# Sheet3_Bat.net
KiCad netlist of a schematic drawn in Altium Designer
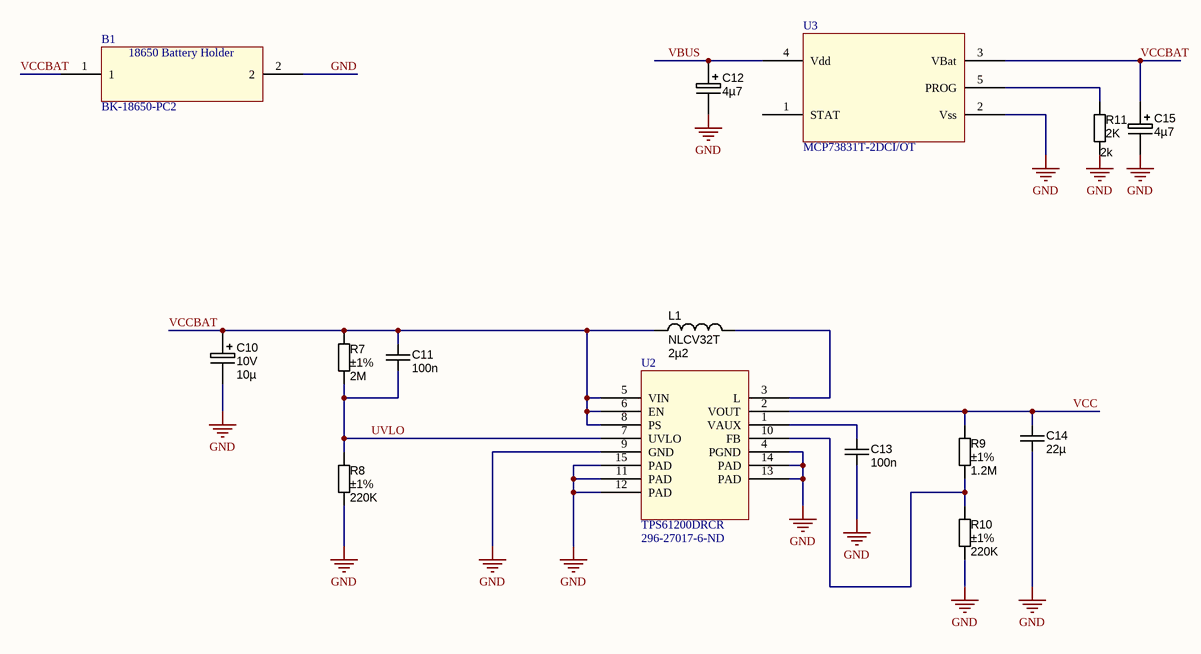
[diagram p0: Sheet3_Bat.SchDoc]

(export (version "E")
  (design (tool "Eeschema 10.0.6"))
  (components
    (comp (ref "B1")
      (value "BK-18650-PC2")
      (footprint "BK-18650-PC2")
      (description "BK-18650-PC2 HOLDER BATT 1/LI-ION PROTECTED")
      (libsource (lib "lightshow") (part "BK-18650-PC2"))
    )
    (comp (ref "C10")
      (value "10µ")
      (footprint "CAPMP2012X150USR")
      (description "Capacitor SMD Tantalum 10uF 20% 10V 0805")
      (fields (field (name "TOLERANCE") "±20%") (field (name "RATINGS") "10V"))
      (libsource (lib "PBL - Capacitors") (part "CAPT_10u_0805_10V"))
    )
    (comp (ref "C11")
      (value "100n")
      (footprint "CAPC2012X135N")
      (description "Capacitor SMD Cer 100nF 10% 100V X7R 0805")
      (fields (field (name "TOLERANCE") "±10%") (field (name "Comment") "approved sub OK"))
      (libsource (lib "PBL - Capacitors") (part "CAPC_100n_0805_X7R_100V_10%"))
    )
    (comp (ref "C12")
      (value "4µ7")
      (footprint "CAPMP3216X180N")
      (description "Capacitor SMD Tantalum 4.7uF 10% 16V 3216-18")
      (fields (field (name "TOLERANCE") "±10%"))
      (libsource (lib "PBL - Capacitors") (part "CAPT_4u7_3216_16V"))
    )
    (comp (ref "C13")
      (value "100n")
      (footprint "CAPC2012X135N")
      (description "Capacitor SMD Cer 100nF 10% 100V X7R 0805")
      (fields (field (name "TOLERANCE") "±10%") (field (name "Comment") "approved sub OK"))
      (libsource (lib "PBL - Capacitors") (part "CAPC_100n_0805_X7R_100V_10%"))
    )
    (comp (ref "C14")
      (value "22µ")
      (footprint "CAPC3225X220N")
      (description "Capacitor SMD Cer 22uF 20% 16V X7R 1210")
      (fields (field (name "TOLERANCE") "±20%") (field (name "MANUFACTURER") "TDK Corporation"))
      (libsource (lib "PBL - Capacitors") (part "CAPC_22u_1210_16V"))
    )
    (comp (ref "C15")
      (value "4µ7")
      (footprint "CAPMP3216X180N")
      (description "Capacitor SMD Tantalum 4.7uF 10% 16V 3216-18")
      (fields (field (name "TOLERANCE") "±10%"))
      (libsource (lib "PBL - Capacitors") (part "CAPT_4u7_3216_16V"))
    )
    (comp (ref "L1")
      (value "NLCV32T")
      (footprint "INDM3225X240N")
      (description "Inductor 2.2uH 1.2A 1210 SMD chip")
      (fields (field (name "TOLERANCE") "±20%") (field (name "ALTIUM_VALUE") "2µ2"))
      (libsource (lib "PBL - Inductors") (part "INDC_2u2_1210_1200mA"))
    )
    (comp (ref "R7")
      (value "2M")
      (footprint "RESC2012X70N")
      (description "Resistor SMD chip 2M Ohm 0.125W 1% 0805")
      (fields (field (name "TOLERANCE") "±1%") (field (name "Comment") "Thick Film"))
      (libsource (lib "PBL - Resistors") (part "RES_2M_0805_1%"))
    )
    (comp (ref "R8")
      (value "220K")
      (footprint "RESC2012X70N")
      (description "Resistor SMD chip 220k Ohm 0.125W 1% 0805")
      (fields (field (name "TOLERANCE") "±1%") (field (name "Comment") "Thick Film"))
      (libsource (lib "PBL - Resistors") (part "RES_220K_0805_1%"))
    )
    (comp (ref "R9")
      (value "1.2M")
      (footprint "RESC2012X70N")
      (description "Resistor SMD chip 1.2M Ohm 0.125W 1% 0805")
      (fields (field (name "TOLERANCE") "±1%") (field (name "Comment") "Thick Film"))
      (libsource (lib "PBL - Resistors") (part "RES_1p2m_0805_1%"))
    )
    (comp (ref "R10")
      (value "220K")
      (footprint "RESC2012X70N")
      (description "Resistor SMD chip 220k Ohm 0.125W 1% 0805")
      (fields (field (name "TOLERANCE") "±1%") (field (name "Comment") "Thick Film"))
      (libsource (lib "PBL - Resistors") (part "RES_220K_0805_1%"))
    )
    (comp (ref "R11")
      (value "2k")
      (footprint "RESC1005X40N")
      (description "Resistor SMD chip 2k Ohm 0.063W 1% 0402")
      (fields (field (name "TOLERANCE") "±5%") (field (name "ALTIUM_VALUE") "2K"))
      (libsource (lib "PBL - Resistors") (part "RES_2K_0402_1%"))
    )
    (comp (ref "U2")
      (value "TPS61200DRCR")
      (footprint "QFN-10_PAD")
      (fields (field (name "SUPPLIER PART NUMBER 1") "296-27017-6-ND"))
      (libsource (lib "lightshow") (part "TPS61200DRCR"))
    )
    (comp (ref "U3")
      (value "MCP73831T-2DCI/OT")
      (footprint "SOT95P270X145-5N")
      (description "IC CONTROLLR LI-ION 4.2V SOT23-5")
      (libsource (lib "lightshow") (part "MCP73831T-2DCI/OT"))
    )
  )
  (nets
    (net (code "1") (name "/UVLO") (class "Default")
      (node (ref "C11") (pin "2") (pintype "passive"))
      (node (ref "R7") (pin "2") (pinfunction "2_2") (pintype "passive"))
      (node (ref "R8") (pin "1") (pinfunction "1_1") (pintype "passive"))
      (node (ref "U2") (pin "7") (pinfunction "UVLO_7") (pintype "passive"))
    )
    (net (code "2") (name "/VBUS") (class "Default")
      (node (ref "C12") (pin "1") (pintype "passive"))
      (node (ref "U3") (pin "4") (pinfunction "Vdd_4") (pintype "power_in"))
    )
    (net (code "3") (name "/VCC") (class "Default")
      (node (ref "C14") (pin "1") (pintype "passive"))
      (node (ref "R9") (pin "1") (pinfunction "1_1") (pintype "passive"))
      (node (ref "U2") (pin "2") (pinfunction "VOUT_2") (pintype "passive"))
    )
    (net (code "4") (name "/VCCBAT") (class "Default")
      (node (ref "B1") (pin "1") (pinfunction "1_1") (pintype "power_in"))
      (node (ref "C10") (pin "1") (pintype "passive"))
      (node (ref "C11") (pin "1") (pintype "passive"))
      (node (ref "C15") (pin "1") (pintype "passive"))
      (node (ref "L1") (pin "1") (pinfunction "1_1") (pintype "passive"))
      (node (ref "R7") (pin "1") (pinfunction "1_1") (pintype "passive"))
      (node (ref "U2") (pin "5") (pinfunction "VIN_5") (pintype "passive"))
      (node (ref "U2") (pin "6") (pinfunction "EN_6") (pintype "passive"))
      (node (ref "U2") (pin "8") (pinfunction "PS_8") (pintype "passive"))
      (node (ref "U3") (pin "3") (pinfunction "VBat_3") (pintype "passive"))
    )
    (net (code "5") (name "GND") (class "Default")
      (node (ref "B1") (pin "2") (pinfunction "2_2") (pintype "power_in"))
      (node (ref "C10") (pin "2") (pintype "passive"))
      (node (ref "C12") (pin "2") (pintype "passive"))
      (node (ref "C13") (pin "2") (pintype "passive"))
      (node (ref "C14") (pin "2") (pintype "passive"))
      (node (ref "C15") (pin "2") (pintype "passive"))
      (node (ref "R10") (pin "2") (pinfunction "2_2") (pintype "passive"))
      (node (ref "R11") (pin "1") (pinfunction "1_1") (pintype "passive"))
      (node (ref "R8") (pin "2") (pinfunction "2_2") (pintype "passive"))
      (node (ref "U2") (pin "11") (pinfunction "PAD_11") (pintype "passive"))
      (node (ref "U2") (pin "12") (pinfunction "PAD_12") (pintype "passive"))
      (node (ref "U2") (pin "13") (pinfunction "PAD_13") (pintype "passive"))
      (node (ref "U2") (pin "14") (pinfunction "PAD_14") (pintype "passive"))
      (node (ref "U2") (pin "15") (pinfunction "PAD_15") (pintype "passive"))
      (node (ref "U2") (pin "4") (pinfunction "PGND_4") (pintype "passive"))
      (node (ref "U2") (pin "9") (pinfunction "GND_9") (pintype "passive"))
      (node (ref "U3") (pin "2") (pinfunction "Vss_2") (pintype "passive"))
    )
    (net (code "6") (name "Net-(U2-FB)") (class "Default")
      (node (ref "R10") (pin "1") (pinfunction "1_1") (pintype "passive"))
      (node (ref "R9") (pin "2") (pinfunction "2_2") (pintype "passive"))
      (node (ref "U2") (pin "10") (pinfunction "FB_10") (pintype "passive"))
    )
    (net (code "7") (name "Net-(U2-L)") (class "Default")
      (node (ref "L1") (pin "2") (pinfunction "2_2") (pintype "passive"))
      (node (ref "U2") (pin "3") (pinfunction "L_3") (pintype "passive"))
    )
    (net (code "8") (name "Net-(U2-VAUX)") (class "Default")
      (node (ref "C13") (pin "1") (pintype "passive"))
      (node (ref "U2") (pin "1") (pinfunction "VAUX_1") (pintype "passive"))
    )
    (net (code "9") (name "Net-(U3-PROG)") (class "Default")
      (node (ref "R11") (pin "2") (pinfunction "2_2") (pintype "passive"))
      (node (ref "U3") (pin "5") (pinfunction "PROG_5") (pintype "passive"))
    )
    (net (code "10") (name "unconnected-(U3-STAT-Pad1)") (class "Default")
      (node (ref "U3") (pin "1") (pinfunction "STAT_1") (pintype "passive"))
    )
  )
)
